# Barun_Gas_Control.net
KiCad netlist of a schematic drawn in Altium Designer
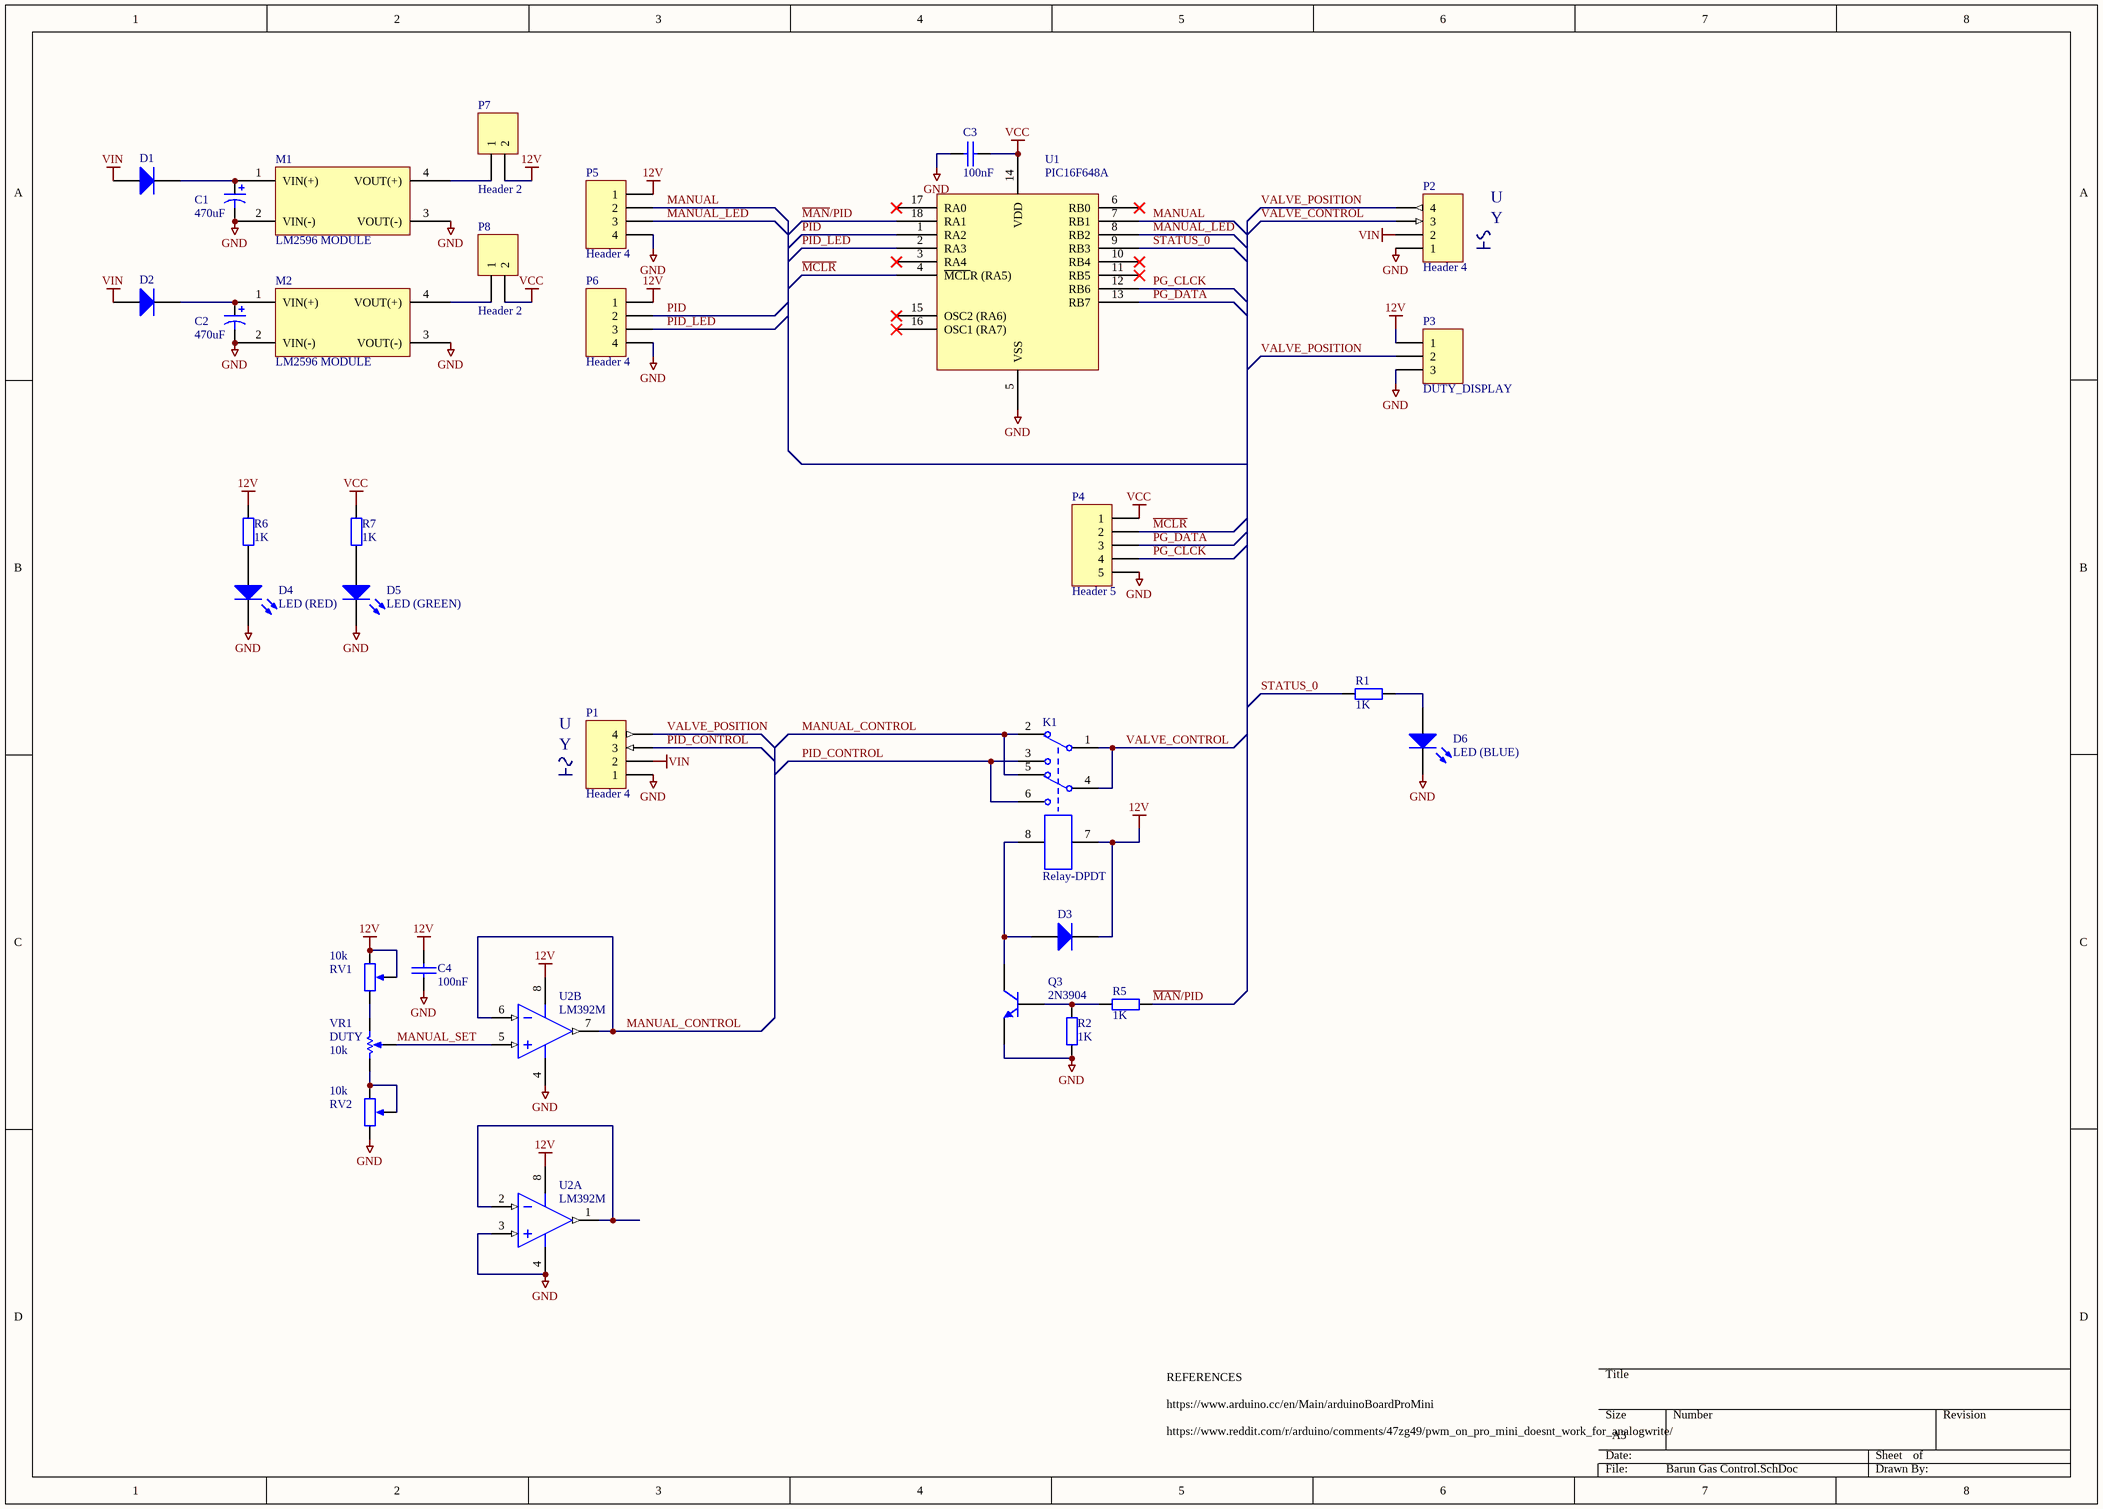
[diagram p0: Barun Gas Control.SchDoc]

(export (version "E")
  (design (tool "Eeschema 10.0.6"))
  (components
    (comp (ref "C1")
      (value "470uF")
      (footprint "RB7.6-15")
      (description "Polarized Capacitor (Surface Mount)")
      (fields (field (name "Comment") "Cap Pol3") (field (name "PUBLISHER") "Altium Limited"))
      (libsource (lib "Miscellaneous Devices") (part "Cap Pol3"))
    )
    (comp (ref "C2")
      (value "470uF")
      (footprint "RB7.6-15")
      (description "Polarized Capacitor (Surface Mount)")
      (fields (field (name "Comment") "Cap Pol3") (field (name "PUBLISHER") "Altium Limited"))
      (libsource (lib "Miscellaneous Devices") (part "Cap Pol3"))
    )
    (comp (ref "C3")
      (value "100nF")
      (footprint "CAP RADIAL 0.200")
      (description "CAPACITOR SMD 0402")
      (libsource (lib "401 CCPA") (part "CAP"))
    )
    (comp (ref "C4")
      (value "100nF")
      (footprint "CAP RADIAL 0.200")
      (description "CAPACITOR SMD 0402")
      (libsource (lib "401 CCPA") (part "CAP"))
    )
    (comp (ref "D1")
      (value "Diode 1N4148")
      (footprint "DO-35")
      (description "High Conductance Fast Diode")
      (fields (field (name "PUBLISHER") "Altium Limited"))
      (libsource (lib "Miscellaneous Devices") (part "Diode 1N4148"))
    )
    (comp (ref "D2")
      (value "Diode 1N4148")
      (footprint "DO-35")
      (description "High Conductance Fast Diode")
      (fields (field (name "PUBLISHER") "Altium Limited"))
      (libsource (lib "Miscellaneous Devices") (part "Diode 1N4148"))
    )
    (comp (ref "D3")
      (value "Diode 1N4148")
      (footprint "DO-35")
      (description "High Conductance Fast Diode")
      (fields (field (name "PUBLISHER") "Altium Limited"))
      (libsource (lib "Miscellaneous Devices") (part "Diode 1N4148"))
    )
    (comp (ref "D4")
      (value "LED (RED)")
      (footprint "LED(3D) 5MM VERTICAL (GREEN)")
      (description "3mm RED LED")
      (fields (field (name "MOUSER PART NO.") "604-WP132XIT") (field (name "FARNELL PART NO.") "1003393"))
      (libsource (lib "NASCO") (part "LED 3mm RED"))
    )
    (comp (ref "D5")
      (value "LED (GREEN)")
      (footprint "LED(3D) 5MM VERTICAL (GREEN)")
      (description "3mm RED LED")
      (fields (field (name "MOUSER PART NO.") "604-WP132XIT") (field (name "FARNELL PART NO.") "1003393"))
      (libsource (lib "NASCO") (part "LED 3mm RED"))
    )
    (comp (ref "D6")
      (value "LED (BLUE)")
      (footprint "LED(3D) 5MM VERTICAL (GREEN)")
      (description "3mm RED LED")
      (fields (field (name "MOUSER PART NO.") "604-WP132XIT") (field (name "FARNELL PART NO.") "1003393"))
      (libsource (lib "NASCO") (part "LED 3mm RED"))
    )
    (comp (ref "K1")
      (value "Relay-DPDT")
      (footprint "RELAY DPDT")
      (description "Altronics S4136 12V Coil")
      (fields
        (field (name "MANUFACTURER") "Generic Components")
        (field (name "MANUFACTURER_1") "Ningbo Forward Relay Corporation LTD")
      )
      (libsource (lib "401 CCPA") (part "Relay-DPDT"))
    )
    (comp (ref "M1")
      (value "LM2596 MODULE")
      (footprint "LM2596 Module")
      (libsource (lib "Barun Gas Control") (part "LM2596 MODULE"))
    )
    (comp (ref "M2")
      (value "LM2596 MODULE")
      (footprint "LM2596 Module")
      (libsource (lib "Barun Gas Control") (part "LM2596 MODULE"))
    )
    (comp (ref "P1")
      (value "Header 4")
      (footprint "5.08mm HEADER 4 Way - With Socket")
      (description "Header, 4-Pin")
      (fields
        (field (name "MANUFACTURER") "Phoenix Contact")
        (field (name "MANUFACTURER PART NO.") "1733596")
      )
      (libsource (lib "") (part "Header 4_2"))
    )
    (comp (ref "P2")
      (value "Header 4")
      (footprint "5.08mm HEADER 4 Way - With Socket")
      (description "Header, 4-Pin")
      (fields
        (field (name "MANUFACTURER") "Phoenix Contact")
        (field (name "MANUFACTURER PART NO.") "1733596")
      )
      (libsource (lib "Miscellaneous Connectors") (part "Header 4"))
    )
    (comp (ref "P3")
      (value "DUTY_DISPLAY")
      (footprint "HDR1X3")
      (description "Header, 3-Pin")
      (fields (field (name "PUBLISHER") "Altium Limited"))
      (libsource (lib "Miscellaneous Connectors") (part "Header 3"))
    )
    (comp (ref "P4")
      (value "Header 5")
      (footprint "HDR1X5")
      (description "Header, 5-Pin")
      (fields (field (name "PUBLISHER") "Altium Limited"))
      (libsource (lib "Miscellaneous Connectors") (part "Header 5"))
    )
    (comp (ref "P5")
      (value "Header 4")
      (footprint "HDR1X4")
      (description "Header, 4-Pin")
      (fields (field (name "PUBLISHER") "Altium Limited"))
      (libsource (lib "") (part "Header 4_1"))
    )
    (comp (ref "P6")
      (value "Header 4")
      (footprint "HDR1X4")
      (description "Header, 4-Pin")
      (fields (field (name "PUBLISHER") "Altium Limited"))
      (libsource (lib "") (part "Header 4_1"))
    )
    (comp (ref "P7")
      (value "Header 2")
      (footprint "HDR1X2")
      (description "Header, 2-Pin")
      (fields (field (name "PUBLISHER") "Altium Limited"))
      (libsource (lib "Miscellaneous Connectors") (part "Header 2"))
    )
    (comp (ref "P8")
      (value "Header 2")
      (footprint "HDR1X2")
      (description "Header, 2-Pin")
      (fields (field (name "PUBLISHER") "Altium Limited"))
      (libsource (lib "Miscellaneous Connectors") (part "Header 2"))
    )
    (comp (ref "Q3")
      (value "2N3904")
      (footprint "TO-92A")
      (description "NPN General Purpose Amplifier")
      (fields (field (name "PUBLISHER") "Altium Limited"))
      (libsource (lib "Miscellaneous Devices") (part "2N3904"))
    )
    (comp (ref "R1")
      (value "1K")
      (footprint "AXIAL-0.4")
      (description "Resistor")
      (fields (field (name "Comment") "Res2") (field (name "PUBLISHER") "Altium Limited"))
      (libsource (lib "") (part "Res2_1"))
    )
    (comp (ref "R2")
      (value "1K")
      (footprint "AXIAL-0.4")
      (description "Resistor")
      (fields (field (name "Comment") "Res2") (field (name "PUBLISHER") "Altium Limited"))
      (libsource (lib "") (part "Res2_2"))
    )
    (comp (ref "R5")
      (value "1K")
      (footprint "AXIAL-0.4")
      (description "Resistor")
      (fields (field (name "Comment") "Res2") (field (name "PUBLISHER") "Altium Limited"))
      (libsource (lib "") (part "Res2_1"))
    )
    (comp (ref "R6")
      (value "1K")
      (footprint "AXIAL-0.4")
      (description "Resistor")
      (fields (field (name "Comment") "Res2") (field (name "PUBLISHER") "Altium Limited"))
      (libsource (lib "Miscellaneous Devices") (part "Res2"))
    )
    (comp (ref "R7")
      (value "1K")
      (footprint "AXIAL-0.4")
      (description "Resistor")
      (fields (field (name "Comment") "Res2") (field (name "PUBLISHER") "Altium Limited"))
      (libsource (lib "Miscellaneous Devices") (part "Res2"))
    )
    (comp (ref "RV1")
      (value "10k")
      (footprint "TRIMMER")
      (description "Variable Resistor")
      (libsource (lib "NASCO") (part "VAR (POT) SMD"))
    )
    (comp (ref "RV2")
      (value "10k")
      (footprint "TRIMMER")
      (description "Variable Resistor")
      (libsource (lib "NASCO") (part "VAR (POT) SMD"))
    )
    (comp (ref "U1")
      (value "PIC16F648A")
      (footprint "DIP-18")
      (description "PIC16F88")
      (fields
        (field (name "MOUSER PART NO.") "579-PIC16F88-E/SS")
        (field (name "FARNELL PART NO.") "9761519")
      )
      (libsource (lib "NASCO") (part "PIC16F87/88"))
    )
    (comp (ref "U2")
      (value "LM392M")
      (footprint "DIP_8")
      (description "Low Power Operational Amplifier/Voltage Comparator, 8-pin Narrow SOIC")
      (fields
        (field (name "MANUFACTURER") "National Semiconductor")
        (field (name "PUBLISHER") "Altium Limited")
      )
      (libsource (lib "NSC Amplifier") (part "LM392M"))
    )
    (comp (ref "VR1")
      (value "DUTY")
      (footprint "HDR1X3")
      (description "Potentiometer")
      (fields (field (name "ALTIUM_VALUE") "10k") (field (name "PUBLISHER") "Altium Limited"))
      (libsource (lib "Miscellaneous Devices") (part "RPot"))
    )
  )
  (nets
    (net (code "1") (name "/MANUAL") (class "Default")
      (node (ref "P5") (pin "2") (pinfunction "2_2") (pintype "passive"))
      (node (ref "U1") (pin "7") (pinfunction "RB1_7") (pintype "passive"))
    )
    (net (code "2") (name "/MANUAL_CONTROL") (class "Default")
      (node (ref "K1") (pin "2") (pinfunction "2_2") (pintype "passive"))
      (node (ref "K1") (pin "5") (pinfunction "5_5") (pintype "passive"))
      (node (ref "U2") (pin "6") (pinfunction "INB-_6") (pintype "input"))
      (node (ref "U2") (pin "7") (pinfunction "OUTB_7") (pintype "output"))
    )
    (net (code "3") (name "/MANUAL_LED") (class "Default")
      (node (ref "P5") (pin "3") (pinfunction "3_3") (pintype "passive"))
      (node (ref "U1") (pin "8") (pinfunction "RB2_8") (pintype "passive"))
    )
    (net (code "4") (name "/MANUAL_SET") (class "Default")
      (node (ref "U2") (pin "5") (pinfunction "INB+_5") (pintype "input"))
      (node (ref "VR1") (pin "3") (pinfunction "TAP_3") (pintype "passive"))
    )
    (net (code "5") (name "/MCLR") (class "Default")
      (node (ref "P4") (pin "2") (pinfunction "2_2") (pintype "passive"))
      (node (ref "U1") (pin "4") (pinfunction "~{MCL}R_(RA5)_4") (pintype "passive"))
    )
    (net (code "6") (name "/PG_CLCK") (class "Default")
      (node (ref "P4") (pin "4") (pinfunction "4_4") (pintype "passive"))
      (node (ref "U1") (pin "12") (pinfunction "RB6_12") (pintype "passive"))
    )
    (net (code "7") (name "/PG_DATA") (class "Default")
      (node (ref "P4") (pin "3") (pinfunction "3_3") (pintype "passive"))
      (node (ref "U1") (pin "13") (pinfunction "RB7_13") (pintype "passive"))
    )
    (net (code "8") (name "/PID") (class "Default")
      (node (ref "P6") (pin "2") (pinfunction "2_2") (pintype "passive"))
      (node (ref "U1") (pin "1") (pinfunction "RA2_1") (pintype "passive"))
    )
    (net (code "9") (name "/PID_CONTROL") (class "Default")
      (node (ref "K1") (pin "3") (pinfunction "3_3") (pintype "passive"))
      (node (ref "K1") (pin "6") (pinfunction "6_6") (pintype "passive"))
      (node (ref "P1") (pin "3") (pinfunction "3_3") (pintype "input"))
    )
    (net (code "10") (name "/PID_LED") (class "Default")
      (node (ref "P6") (pin "3") (pinfunction "3_3") (pintype "passive"))
      (node (ref "U1") (pin "2") (pinfunction "RA3_2") (pintype "passive"))
    )
    (net (code "11") (name "/STATUS_0") (class "Default")
      (node (ref "R1") (pin "2") (pinfunction "2_2") (pintype "passive"))
      (node (ref "U1") (pin "9") (pinfunction "RB3_9") (pintype "passive"))
    )
    (net (code "12") (name "/VALVE_CONTROL") (class "Default")
      (node (ref "K1") (pin "1") (pinfunction "1_1") (pintype "passive"))
      (node (ref "K1") (pin "4") (pinfunction "4_4") (pintype "passive"))
      (node (ref "P2") (pin "3") (pinfunction "3_3") (pintype "input"))
    )
    (net (code "13") (name "/VALVE_POSITION") (class "Default")
      (node (ref "P1") (pin "4") (pinfunction "4_4") (pintype "output"))
      (node (ref "P2") (pin "4") (pinfunction "4_4") (pintype "output"))
      (node (ref "P3") (pin "2") (pinfunction "2_2") (pintype "passive"))
    )
    (net (code "14") (name "/~{MAN}{slash}PID") (class "Default")
      (node (ref "R5") (pin "1") (pinfunction "1_1") (pintype "passive"))
      (node (ref "U1") (pin "18") (pinfunction "RA1_18") (pintype "passive"))
    )
    (net (code "15") (name "12V") (class "Default")
      (node (ref "C4") (pin "2") (pinfunction "2_2") (pintype "passive"))
      (node (ref "D3") (pin "2") (pinfunction "K_2") (pintype "passive"))
      (node (ref "K1") (pin "7") (pinfunction "7_7") (pintype "passive"))
      (node (ref "P3") (pin "1") (pinfunction "1_1") (pintype "passive"))
      (node (ref "P5") (pin "1") (pinfunction "1_1") (pintype "passive"))
      (node (ref "P6") (pin "1") (pinfunction "1_1") (pintype "passive"))
      (node (ref "P7") (pin "2") (pinfunction "2_2") (pintype "passive"))
      (node (ref "R6") (pin "1") (pinfunction "1_1") (pintype "passive"))
      (node (ref "RV1") (pin "1") (pinfunction "1_1") (pintype "passive"))
      (node (ref "RV1") (pin "2") (pinfunction "2_2") (pintype "passive"))
      (node (ref "U2") (pin "8") (pinfunction "V+_8") (pintype "power_in"))
    )
    (net (code "16") (name "GND") (class "Default")
      (node (ref "C1") (pin "2") (pinfunction "2_2") (pintype "passive"))
      (node (ref "C2") (pin "2") (pinfunction "2_2") (pintype "passive"))
      (node (ref "C3") (pin "1") (pinfunction "1_1") (pintype "passive"))
      (node (ref "C4") (pin "1") (pinfunction "1_1") (pintype "passive"))
      (node (ref "D4") (pin "2") (pinfunction "K_2") (pintype "passive"))
      (node (ref "D5") (pin "2") (pinfunction "K_2") (pintype "passive"))
      (node (ref "D6") (pin "2") (pinfunction "K_2") (pintype "passive"))
      (node (ref "M1") (pin "2") (pinfunction "VIN(-)_2") (pintype "passive"))
      (node (ref "M1") (pin "3") (pinfunction "VOUT(-)_3") (pintype "passive"))
      (node (ref "M2") (pin "2") (pinfunction "VIN(-)_2") (pintype "passive"))
      (node (ref "M2") (pin "3") (pinfunction "VOUT(-)_3") (pintype "passive"))
      (node (ref "P1") (pin "1") (pinfunction "1_1") (pintype "passive"))
      (node (ref "P2") (pin "1") (pinfunction "1_1") (pintype "passive"))
      (node (ref "P3") (pin "3") (pinfunction "3_3") (pintype "passive"))
      (node (ref "P4") (pin "5") (pinfunction "5_5") (pintype "passive"))
      (node (ref "P5") (pin "4") (pinfunction "4_4") (pintype "passive"))
      (node (ref "P6") (pin "4") (pinfunction "4_4") (pintype "passive"))
      (node (ref "Q3") (pin "1") (pinfunction "E_1") (pintype "passive"))
      (node (ref "R2") (pin "1") (pinfunction "1_1") (pintype "passive"))
      (node (ref "RV2") (pin "3") (pinfunction "3_3") (pintype "passive"))
      (node (ref "U1") (pin "5") (pinfunction "VSS_5") (pintype "passive"))
      (node (ref "U2") (pin "3") (pinfunction "INA+_3") (pintype "input"))
      (node (ref "U2") (pin "4") (pinfunction "GND_4") (pintype "power_in"))
    )
    (net (code "17") (name "Net-(D1-K)") (class "Default")
      (node (ref "C1") (pin "1") (pinfunction "1_1") (pintype "passive"))
      (node (ref "D1") (pin "2") (pinfunction "K_2") (pintype "passive"))
      (node (ref "M1") (pin "1") (pinfunction "VIN(+)_1") (pintype "passive"))
    )
    (net (code "18") (name "Net-(D2-K)") (class "Default")
      (node (ref "C2") (pin "1") (pinfunction "1_1") (pintype "passive"))
      (node (ref "D2") (pin "2") (pinfunction "K_2") (pintype "passive"))
      (node (ref "M2") (pin "1") (pinfunction "VIN(+)_1") (pintype "passive"))
    )
    (net (code "19") (name "Net-(D3-A)") (class "Default")
      (node (ref "D3") (pin "1") (pinfunction "A_1") (pintype "passive"))
      (node (ref "K1") (pin "8") (pinfunction "8_8") (pintype "passive"))
      (node (ref "Q3") (pin "3") (pinfunction "C_3") (pintype "passive"))
    )
    (net (code "20") (name "Net-(D4-A)") (class "Default")
      (node (ref "D4") (pin "1") (pinfunction "A_1") (pintype "passive"))
      (node (ref "R6") (pin "2") (pinfunction "2_2") (pintype "passive"))
    )
    (net (code "21") (name "Net-(D5-A)") (class "Default")
      (node (ref "D5") (pin "1") (pinfunction "A_1") (pintype "passive"))
      (node (ref "R7") (pin "2") (pinfunction "2_2") (pintype "passive"))
    )
    (net (code "22") (name "Net-(D6-A)") (class "Default")
      (node (ref "D6") (pin "1") (pinfunction "A_1") (pintype "passive"))
      (node (ref "R1") (pin "1") (pinfunction "1_1") (pintype "passive"))
    )
    (net (code "23") (name "Net-(M1-VOUT(+))") (class "Default")
      (node (ref "M1") (pin "4") (pinfunction "VOUT(+)_4") (pintype "passive"))
      (node (ref "P7") (pin "1") (pinfunction "1_1") (pintype "passive"))
    )
    (net (code "24") (name "Net-(M2-VOUT(+))") (class "Default")
      (node (ref "M2") (pin "4") (pinfunction "VOUT(+)_4") (pintype "passive"))
      (node (ref "P8") (pin "1") (pinfunction "1_1") (pintype "passive"))
    )
    (net (code "25") (name "Net-(Q3-B)") (class "Default")
      (node (ref "Q3") (pin "2") (pinfunction "B_2") (pintype "passive"))
      (node (ref "R2") (pin "2") (pinfunction "2_2") (pintype "passive"))
      (node (ref "R5") (pin "2") (pinfunction "2_2") (pintype "passive"))
    )
    (net (code "26") (name "Net-(U2A-INA-)") (class "Default")
      (node (ref "U2") (pin "1") (pinfunction "OUTA_1") (pintype "output"))
      (node (ref "U2") (pin "2") (pinfunction "INA-_2") (pintype "input"))
    )
    (net (code "27") (name "Net-(VR1-BOT)") (class "Default")
      (node (ref "RV2") (pin "1") (pinfunction "1_1") (pintype "passive"))
      (node (ref "RV2") (pin "2") (pinfunction "2_2") (pintype "passive"))
      (node (ref "VR1") (pin "2") (pinfunction "BOT_2") (pintype "passive"))
    )
    (net (code "28") (name "Net-(VR1-TOP)") (class "Default")
      (node (ref "RV1") (pin "3") (pinfunction "3_3") (pintype "passive"))
      (node (ref "VR1") (pin "1") (pinfunction "TOP_1") (pintype "passive"))
    )
    (net (code "29") (name "VCC") (class "Default")
      (node (ref "C3") (pin "2") (pinfunction "2_2") (pintype "passive"))
      (node (ref "P4") (pin "1") (pinfunction "1_1") (pintype "passive"))
      (node (ref "P8") (pin "2") (pinfunction "2_2") (pintype "passive"))
      (node (ref "R7") (pin "1") (pinfunction "1_1") (pintype "passive"))
      (node (ref "U1") (pin "14") (pinfunction "VDD_14") (pintype "passive"))
    )
    (net (code "30") (name "VIN") (class "Default")
      (node (ref "D1") (pin "1") (pinfunction "A_1") (pintype "passive"))
      (node (ref "D2") (pin "1") (pinfunction "A_1") (pintype "passive"))
      (node (ref "P1") (pin "2") (pinfunction "2_2") (pintype "passive"))
      (node (ref "P2") (pin "2") (pinfunction "2_2") (pintype "passive"))
    )
    (net (code "31") (name "unconnected-(U1-OSC1_(RA7)-Pad16)") (class "Default")
      (node (ref "U1") (pin "16") (pinfunction "OSC1_(RA7)_16") (pintype "passive+no_connect"))
    )
    (net (code "32") (name "unconnected-(U1-OSC2_(RA6)-Pad15)") (class "Default")
      (node (ref "U1") (pin "15") (pinfunction "OSC2_(RA6)_15") (pintype "passive+no_connect"))
    )
    (net (code "33") (name "unconnected-(U1-RA0-Pad17)") (class "Default")
      (node (ref "U1") (pin "17") (pinfunction "RA0_17") (pintype "passive+no_connect"))
    )
    (net (code "34") (name "unconnected-(U1-RA4-Pad3)") (class "Default")
      (node (ref "U1") (pin "3") (pinfunction "RA4_3") (pintype "passive+no_connect"))
    )
    (net (code "35") (name "unconnected-(U1-RB0-Pad6)") (class "Default")
      (node (ref "U1") (pin "6") (pinfunction "RB0_6") (pintype "passive+no_connect"))
    )
    (net (code "36") (name "unconnected-(U1-RB4-Pad10)") (class "Default")
      (node (ref "U1") (pin "10") (pinfunction "RB4_10") (pintype "passive+no_connect"))
    )
    (net (code "37") (name "unconnected-(U1-RB5-Pad11)") (class "Default")
      (node (ref "U1") (pin "11") (pinfunction "RB5_11") (pintype "passive+no_connect"))
    )
  )
)
